# SCH_card_2024-12-13.net
KiCad netlist of a schematic drawn in EasyEDA
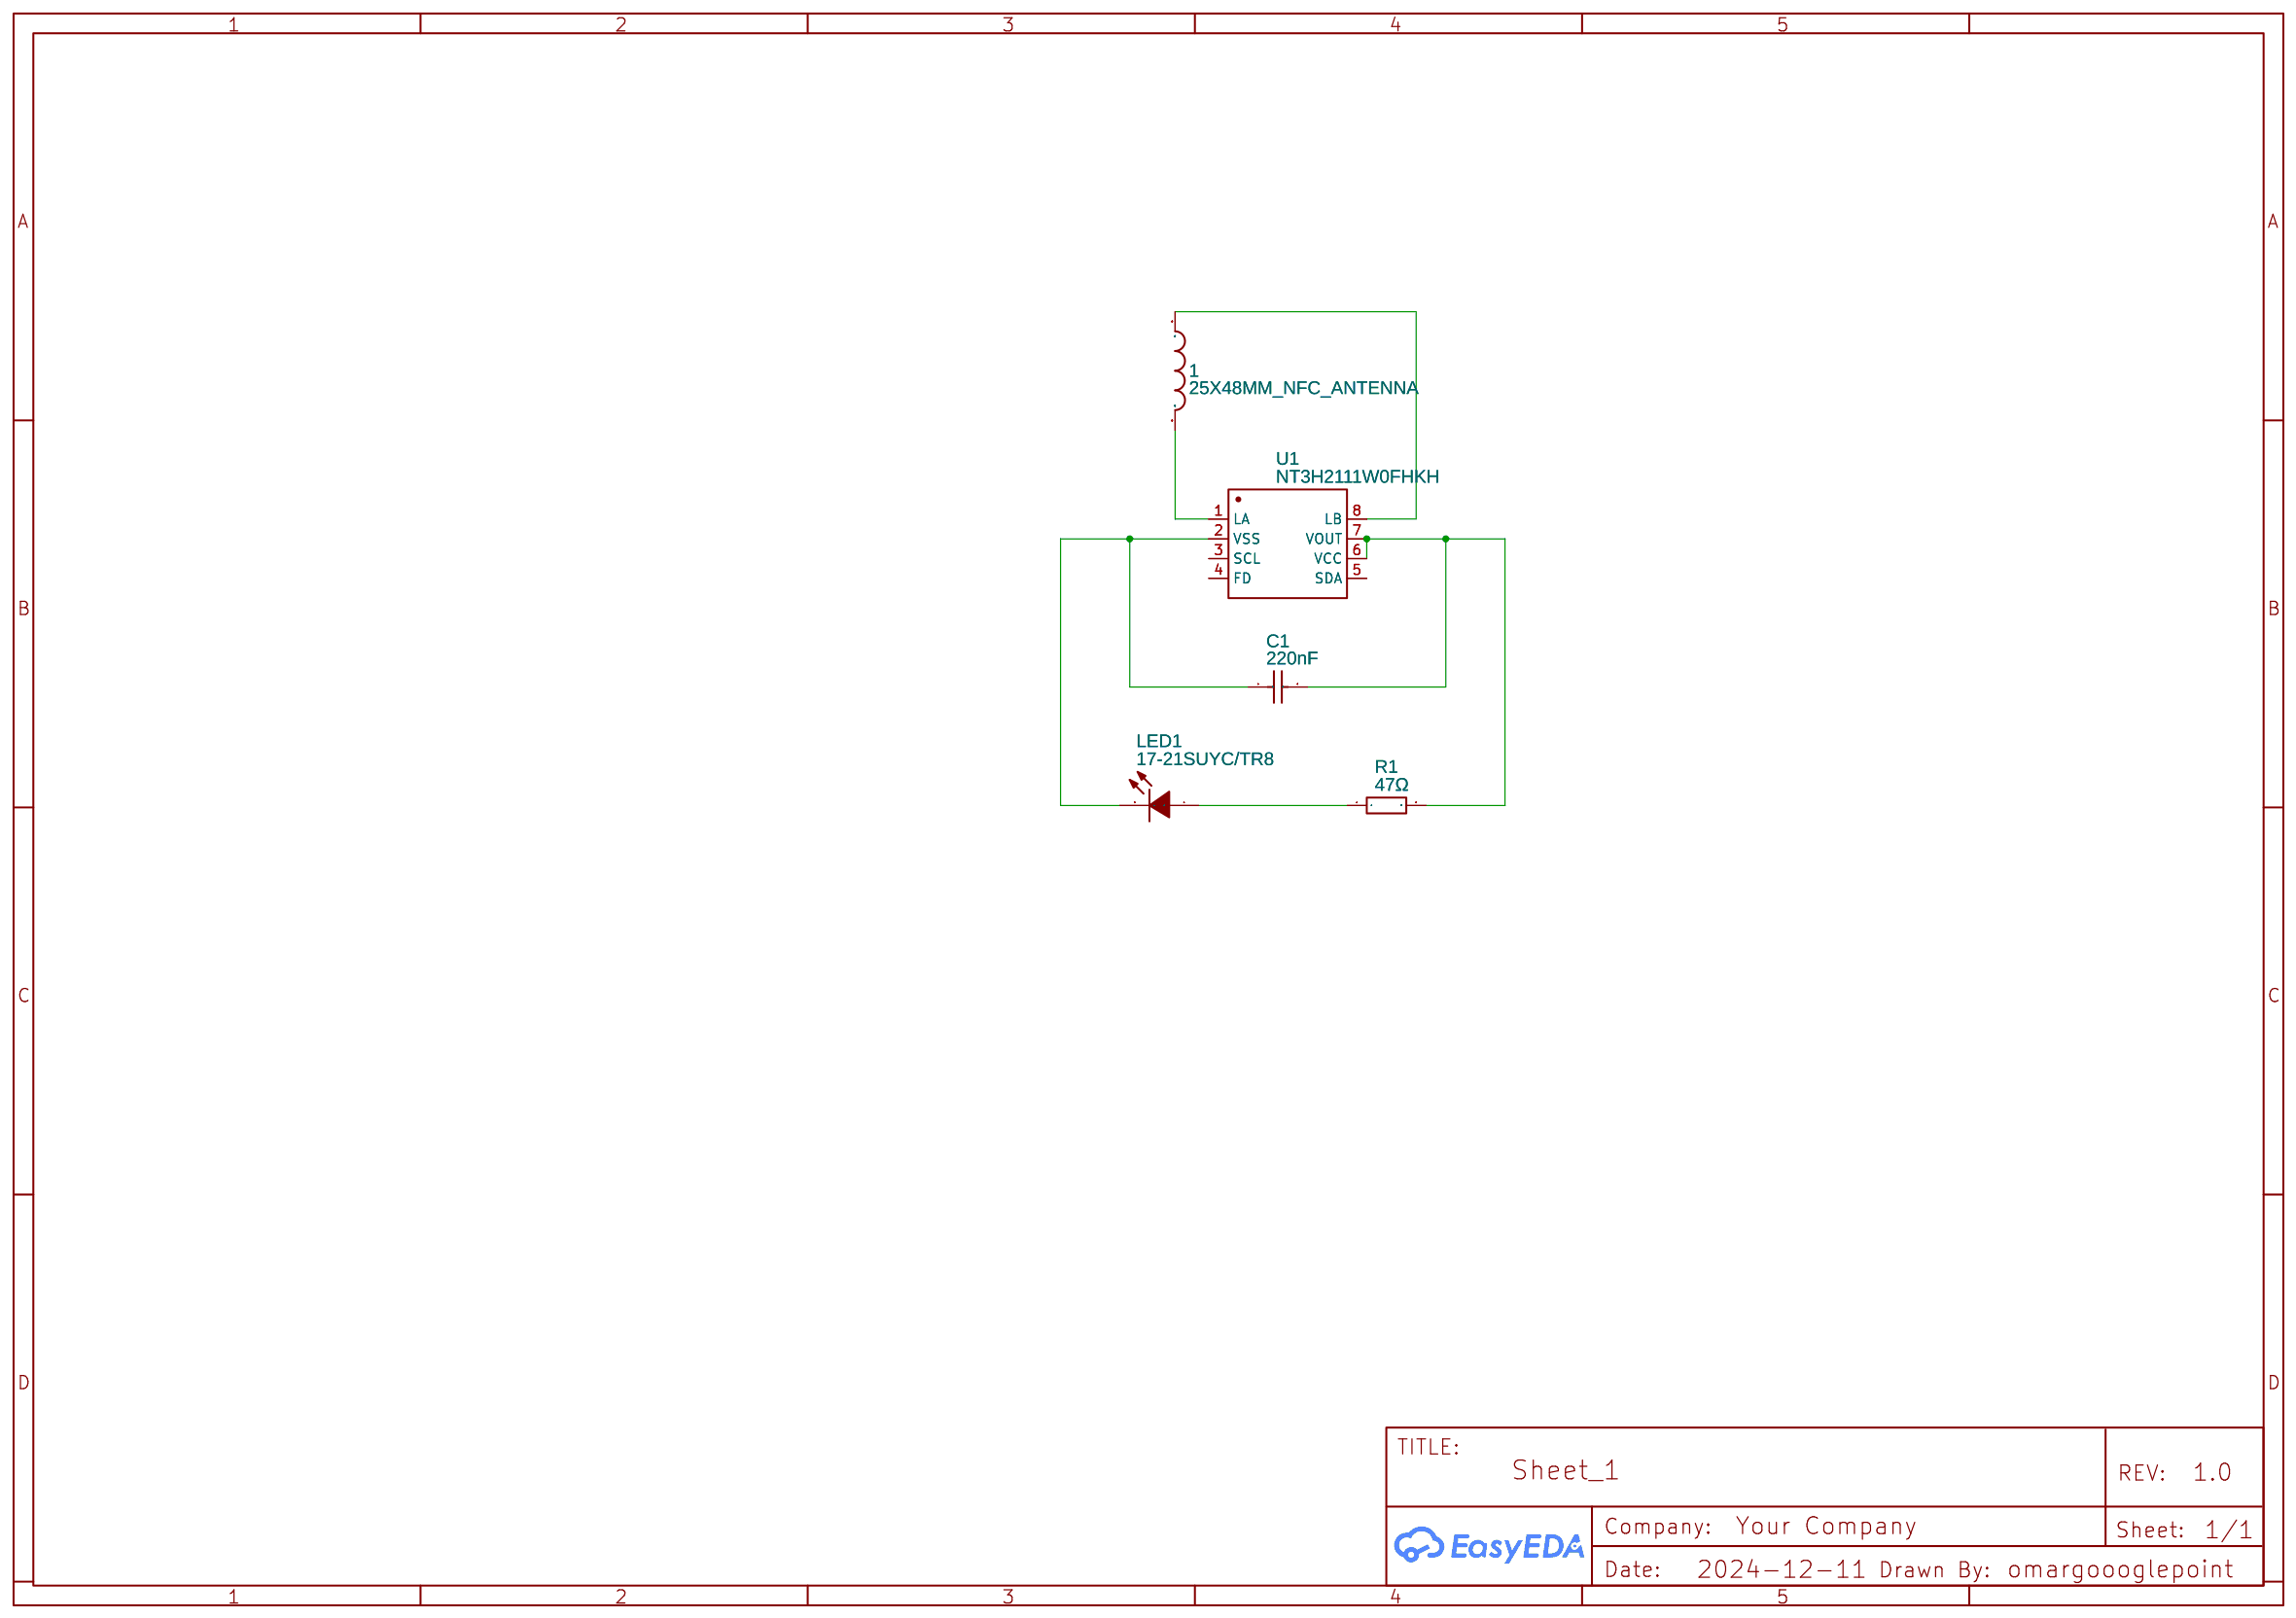
[diagram p0: schematic sheet]

(export (version "E")
  (design (tool "Eeschema 10.0.6"))
  (components
    (comp (ref "1") (value "25X48MM_NFC_ANTENNA") (libsource (lib "") (part "25X48MM_NFC_ANTENNA")))
    (comp (ref "C1")
      (value "220nF")
      (fields
        (field (name "Manufacturer Part") "CL10B224KA8NNNC")
        (field (name "Manufacturer") "SAMSUNG(三星)")
      )
      (libsource (lib "") (part "CL10B224KA8NNNC"))
    )
    (comp (ref "LED1")
      (value "17-21SUYC/TR8")
      (fields (field (name "Manufacturer Part") "KT-0805黄灯") (field (name "Manufacturer") "KENTO"))
      (libsource (lib "") (part "17-21SUYC/TR8"))
    )
    (comp (ref "R1")
      (value "47Ω")
      (fields
        (field (name "Manufacturer Part") "0603WAF470JT5E")
        (field (name "Manufacturer") "UNI-ROYAL(厚声)")
      )
      (libsource (lib "") (part "0603WAF470JT5E"))
    )
    (comp (ref "U1")
      (value "NT3H2111W0FHKH")
      (fields (field (name "Manufacturer") "NXP(恩智浦)"))
      (libsource (lib "") (part "NT3H2111W0FHKH"))
    )
  )
  (nets
    (net (code "1") (name "Net-(LED1-+)") (class "Default")
      (node (ref "LED1") (pin "1") (pinfunction "+_1") (pintype "unspecified"))
      (node (ref "R1") (pin "1") (pinfunction "1_1") (pintype "input"))
    )
    (net (code "2") (name "Net-(LED1--)") (class "Default")
      (node (ref "C1") (pin "1") (pinfunction "1_1") (pintype "input"))
      (node (ref "LED1") (pin "2") (pinfunction "-_2") (pintype "unspecified"))
      (node (ref "U1") (pin "2") (pinfunction "VSS_2") (pintype "unspecified"))
    )
    (net (code "3") (name "Net-(U1-LA)") (class "Default")
      (node (ref "1") (pin "P$2") (pinfunction "P$2_P$2") (pintype "bidirectional"))
      (node (ref "U1") (pin "1") (pinfunction "LA_1") (pintype "unspecified"))
    )
    (net (code "4") (name "Net-(U1-LB)") (class "Default")
      (node (ref "1") (pin "P$1") (pinfunction "P$1_P$1") (pintype "bidirectional"))
      (node (ref "U1") (pin "8") (pinfunction "LB_8") (pintype "unspecified"))
    )
    (net (code "5") (name "Net-(U1-VCC)") (class "Default")
      (node (ref "C1") (pin "2") (pinfunction "2_2") (pintype "input"))
      (node (ref "R1") (pin "2") (pinfunction "2_2") (pintype "input"))
      (node (ref "U1") (pin "6") (pinfunction "VCC_6") (pintype "unspecified"))
      (node (ref "U1") (pin "7") (pinfunction "VOUT_7") (pintype "unspecified"))
    )
    (net (code "6") (name "unconnected-(U1-FD-Pad4)") (class "Default")
      (node (ref "U1") (pin "4") (pinfunction "FD_4") (pintype "unspecified"))
    )
    (net (code "7") (name "unconnected-(U1-SCL-Pad3)") (class "Default")
      (node (ref "U1") (pin "3") (pinfunction "SCL_3") (pintype "unspecified"))
    )
    (net (code "8") (name "unconnected-(U1-SDA-Pad5)") (class "Default")
      (node (ref "U1") (pin "5") (pinfunction "SDA_5") (pintype "unspecified"))
    )
  )
)
